# Blend_VCO.net
KiCad netlist of a schematic drawn in Altium Designer
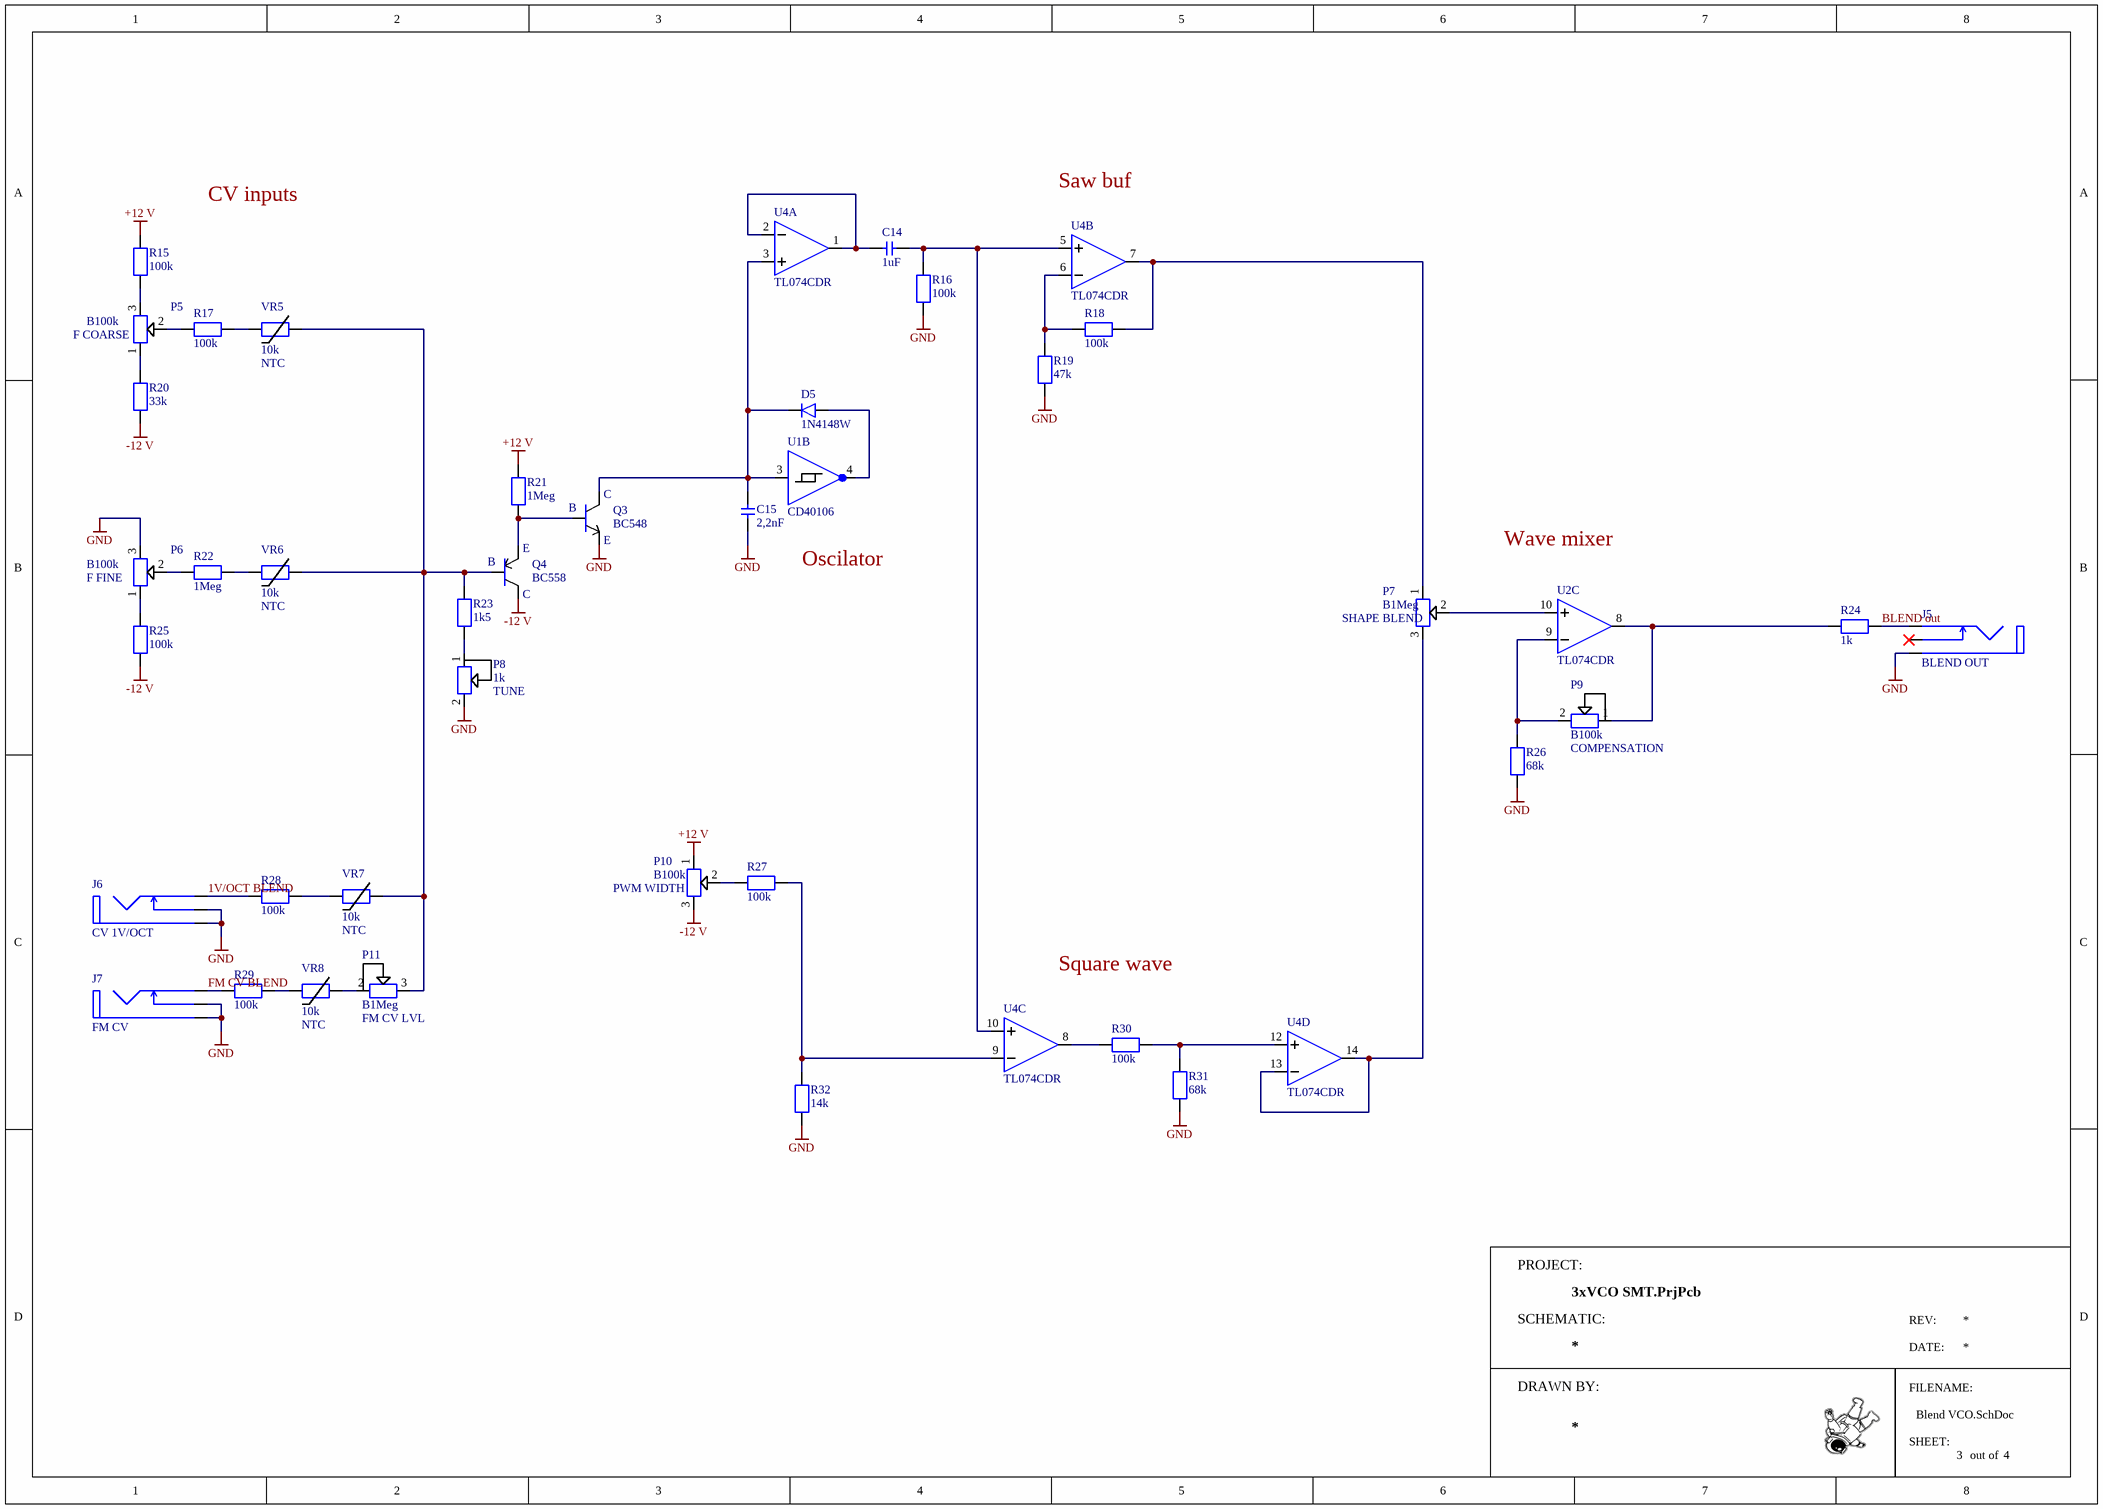
[diagram p0: Blend VCO.SchDoc]

(export (version "E")
  (design (tool "Eeschema 10.0.6"))
  (components
    (comp (ref "C14")
      (value "1uF")
      (footprint "Cap SMD 0805")
      (description "SMD Capacitor Non-Polarised 0805 Package")
      (fields (field (name "Comment") "CAP"))
      (libsource (lib "Generic components") (part "Capacitor SMD 0805"))
    )
    (comp (ref "C15")
      (value "2,2nF")
      (footprint "Cap SMD 0805")
      (description "SMD Capacitor Non-Polarised 0805 Package")
      (fields (field (name "Comment") "CAP"))
      (libsource (lib "Generic components") (part "Capacitor SMD 0805"))
    )
    (comp (ref "D5")
      (value "DIODE")
      (footprint "SOD-123")
      (description "Generic SMD Diode SOD123 Package")
      (fields (field (name "MODEL") "1N4148W"))
      (libsource (lib "Diodes") (part "Diode SMD SOD123"))
    )
    (comp (ref "J5")
      (value "JACK Mono")
      (footprint "PJ301M")
      (description "PJ301M Eurorack 3,5 mm Patch Socket PCB Mount")
      (fields (field (name "LABEL") "BLEND OUT"))
      (libsource (lib "Connectors") (part "PJ301M"))
    )
    (comp (ref "J6")
      (value "JACK Mono")
      (footprint "PJ301M")
      (description "PJ301M Eurorack 3,5 mm Patch Socket PCB Mount")
      (fields (field (name "LABEL") "CV 1V/OCT"))
      (libsource (lib "Connectors") (part "PJ301M"))
    )
    (comp (ref "J7")
      (value "JACK Mono")
      (footprint "PJ301M")
      (description "PJ301M Eurorack 3,5 mm Patch Socket PCB Mount")
      (fields (field (name "LABEL") "FM CV"))
      (libsource (lib "Connectors") (part "PJ301M"))
    )
    (comp (ref "P5")
      (value "B100k")
      (footprint "9 mm PCB Potentiometer")
      (description "PCB Mount 9mm Mono Potentiometer THT")
      (fields (field (name "PARAMETER") "F COARSE") (field (name "Comment") "Mono Pot"))
      (libsource (lib "Potentiometers") (part "Potentiometer 9 mm"))
    )
    (comp (ref "P6")
      (value "B100k")
      (footprint "9 mm PCB Potentiometer")
      (description "PCB Mount 9mm Mono Potentiometer THT")
      (fields (field (name "PARAMETER") "F FINE") (field (name "Comment") "Mono Pot"))
      (libsource (lib "Potentiometers") (part "Potentiometer 9 mm"))
    )
    (comp (ref "P7")
      (value "B1Meg")
      (footprint "9 mm PCB Potentiometer")
      (description "PCB Mount 9mm Mono Potentiometer THT")
      (fields (field (name "PARAMETER") "SHAPE BLEND") (field (name "Comment") "Mono Pot"))
      (libsource (lib "Potentiometers") (part "Potentiometer 9 mm"))
    )
    (comp (ref "P8")
      (value "1k")
      (footprint "Multiturn Potentiometer inline")
      (description "PCB Mount Multiturn Trimmer Potentiometer Top Adjustable as Variable Resistor Clockwise Increase")
      (fields (field (name "PARAMETER") "TUNE") (field (name "Comment") "VR"))
      (libsource (lib "Potentiometers") (part "VR A Multiturn THT"))
    )
    (comp (ref "P9")
      (value "B100k")
      (footprint "9 mm PCB Potentiometer")
      (description "PCB Mount 9mm Mono Potentiometer THT as Variable Resistor Clockwise Increase")
      (fields (field (name "PARAMETER") "COMPENSATION") (field (name "Comment") "VR"))
      (libsource (lib "Potentiometers") (part "VR A 9 mm"))
    )
    (comp (ref "P10")
      (value "B100k")
      (footprint "9 mm PCB Potentiometer")
      (description "PCB Mount 9mm Mono Potentiometer THT")
      (fields (field (name "PARAMETER") "PWM WIDTH") (field (name "Comment") "Mono Pot"))
      (libsource (lib "Potentiometers") (part "Potentiometer 9 mm"))
    )
    (comp (ref "P11")
      (value "B1Meg")
      (footprint "9 mm PCB Potentiometer")
      (description "PCB Mount 9mm Mono Potentiometer THT as Variable Resistor Clockwise Decrease")
      (fields (field (name "PARAMETER") "FM CV LVL") (field (name "Comment") "VR"))
      (libsource (lib "Potentiometers") (part "VR B 9 mm"))
    )
    (comp (ref "Q3")
      (value "BC548")
      (footprint "TO-92 wide")
      (description "BC548 NPN Transistor THT TO-92 Package")
      (libsource (lib "Transistors") (part "BC548"))
    )
    (comp (ref "Q4")
      (value "BC558")
      (footprint "TO-92 wide")
      (description "BC558 PNP Transistor THT TO-92 Package")
      (libsource (lib "Transistors") (part "BC558"))
    )
    (comp (ref "R15")
      (value "100k")
      (footprint "Resistor SMD 0805")
      (description "SMD Resistor 0805 package")
      (fields (field (name "Comment") "RES"))
      (libsource (lib "Generic components") (part "Resistor SMD 0805"))
    )
    (comp (ref "R16")
      (value "100k")
      (footprint "Resistor SMD 0805")
      (description "SMD Resistor 0805 package")
      (fields (field (name "Comment") "RES"))
      (libsource (lib "Generic components") (part "Resistor SMD 0805"))
    )
    (comp (ref "R17")
      (value "100k")
      (footprint "Resistor SMD 0805")
      (description "SMD Resistor 0805 package")
      (fields (field (name "Comment") "RES"))
      (libsource (lib "Generic components") (part "Resistor SMD 0805"))
    )
    (comp (ref "R18")
      (value "100k")
      (footprint "Resistor SMD 0805")
      (description "SMD Resistor 0805 package")
      (fields (field (name "Comment") "RES"))
      (libsource (lib "Generic components") (part "Resistor SMD 0805"))
    )
    (comp (ref "R19")
      (value "47k")
      (footprint "Resistor SMD 0805")
      (description "SMD Resistor 0805 package")
      (fields (field (name "Comment") "RES"))
      (libsource (lib "Generic components") (part "Resistor SMD 0805"))
    )
    (comp (ref "R20")
      (value "33k")
      (footprint "Resistor SMD 0805")
      (description "SMD Resistor 0805 package")
      (fields (field (name "Comment") "RES"))
      (libsource (lib "Generic components") (part "Resistor SMD 0805"))
    )
    (comp (ref "R21")
      (value "1Meg")
      (footprint "Resistor SMD 0805")
      (description "SMD Resistor 0805 package")
      (fields (field (name "Comment") "RES"))
      (libsource (lib "Generic components") (part "Resistor SMD 0805"))
    )
    (comp (ref "R22")
      (value "1Meg")
      (footprint "Resistor SMD 0805")
      (description "SMD Resistor 0805 package")
      (fields (field (name "Comment") "RES"))
      (libsource (lib "Generic components") (part "Resistor SMD 0805"))
    )
    (comp (ref "R23")
      (value "1k5")
      (footprint "Resistor SMD 0805")
      (description "SMD Resistor 0805 package")
      (fields (field (name "Comment") "RES"))
      (libsource (lib "Generic components") (part "Resistor SMD 0805"))
    )
    (comp (ref "R24")
      (value "1k")
      (footprint "Resistor SMD 0805")
      (description "SMD Resistor 0805 package")
      (fields (field (name "Comment") "RES"))
      (libsource (lib "Generic components") (part "Resistor SMD 0805"))
    )
    (comp (ref "R25")
      (value "100k")
      (footprint "Resistor SMD 0805")
      (description "SMD Resistor 0805 package")
      (fields (field (name "Comment") "RES"))
      (libsource (lib "Generic components") (part "Resistor SMD 0805"))
    )
    (comp (ref "R26")
      (value "68k")
      (footprint "Resistor SMD 0805")
      (description "SMD Resistor 0805 package")
      (fields (field (name "Comment") "RES"))
      (libsource (lib "Generic components") (part "Resistor SMD 0805"))
    )
    (comp (ref "R27")
      (value "100k")
      (footprint "Resistor SMD 0805")
      (description "SMD Resistor 0805 package")
      (fields (field (name "Comment") "RES"))
      (libsource (lib "Generic components") (part "Resistor SMD 0805"))
    )
    (comp (ref "R28")
      (value "100k")
      (footprint "Resistor SMD 0805")
      (description "SMD Resistor 0805 package")
      (fields (field (name "Comment") "RES"))
      (libsource (lib "Generic components") (part "Resistor SMD 0805"))
    )
    (comp (ref "R29")
      (value "100k")
      (footprint "Resistor SMD 0805")
      (description "SMD Resistor 0805 package")
      (fields (field (name "Comment") "RES"))
      (libsource (lib "Generic components") (part "Resistor SMD 0805"))
    )
    (comp (ref "R30")
      (value "100k")
      (footprint "Resistor SMD 0805")
      (description "SMD Resistor 0805 package")
      (fields (field (name "Comment") "RES"))
      (libsource (lib "Generic components") (part "Resistor SMD 0805"))
    )
    (comp (ref "R31")
      (value "68k")
      (footprint "Resistor SMD 0805")
      (description "SMD Resistor 0805 package")
      (fields (field (name "Comment") "RES"))
      (libsource (lib "Generic components") (part "Resistor SMD 0805"))
    )
    (comp (ref "R32")
      (value "14k")
      (footprint "Resistor SMD 0805")
      (description "SMD Resistor 0805 package")
      (fields (field (name "Comment") "RES"))
      (libsource (lib "Generic components") (part "Resistor SMD 0805"))
    )
    (comp (ref "U1")
      (value "CD40106")
      (footprint "DIP-14 socket")
      (description "CD40106 Hex Schmitt Trigger Inverter DIP-14 Package")
      (libsource (lib "ICs") (part "CD40106 DIP-14"))
    )
    (comp (ref "U2")
      (value "TL074CDR")
      (footprint "SOIC14")
      (description "TL074CDR Quad Op-Amp SOIC14 Package")
      (libsource (lib "") (part "TL074CDR SOIC14_1"))
    )
    (comp (ref "U4")
      (value "TL074CDR")
      (footprint "SOIC14")
      (description "TL074CDR Quad Op-Amp SOIC14 Package")
      (libsource (lib "") (part "TL074CDR SOIC14_1"))
    )
    (comp (ref "VR5")
      (value "NTC")
      (footprint "Thermistor SMD 0805")
      (description "SMD NTC Thermistor 0805 package")
      (fields (field (name "ALTIUM_VALUE") "10k"))
      (libsource (lib "Generic components") (part "Thermistor NTC SMD 0805"))
    )
    (comp (ref "VR6")
      (value "NTC")
      (footprint "Thermistor SMD 0805")
      (description "SMD NTC Thermistor 0805 package")
      (fields (field (name "ALTIUM_VALUE") "10k"))
      (libsource (lib "Generic components") (part "Thermistor NTC SMD 0805"))
    )
    (comp (ref "VR7")
      (value "NTC")
      (footprint "Thermistor SMD 0805")
      (description "SMD NTC Thermistor 0805 package")
      (fields (field (name "ALTIUM_VALUE") "10k"))
      (libsource (lib "Generic components") (part "Thermistor NTC SMD 0805"))
    )
    (comp (ref "VR8")
      (value "NTC")
      (footprint "Thermistor SMD 0805")
      (description "SMD NTC Thermistor 0805 package")
      (fields (field (name "ALTIUM_VALUE") "10k"))
      (libsource (lib "Generic components") (part "Thermistor NTC SMD 0805"))
    )
  )
  (nets
    (net (code "1") (name "+12 V") (class "Default")
      (node (ref "P10") (pin "1") (pintype "passive"))
      (node (ref "R15") (pin "2") (pintype "passive"))
      (node (ref "R21") (pin "1") (pintype "passive"))
    )
    (net (code "2") (name "-12 V") (class "Default")
      (node (ref "P10") (pin "3") (pintype "passive"))
      (node (ref "Q4") (pin "1") (pintype "passive"))
      (node (ref "R20") (pin "1") (pintype "passive"))
      (node (ref "R25") (pin "1") (pintype "passive"))
    )
    (net (code "3") (name "/1V{slash}OCT BLEND") (class "Default")
      (node (ref "J6") (pin "3") (pintype "passive"))
      (node (ref "R28") (pin "2") (pintype "passive"))
    )
    (net (code "4") (name "/BLEND out") (class "Default")
      (node (ref "J5") (pin "3") (pintype "passive"))
      (node (ref "R24") (pin "2") (pintype "passive"))
    )
    (net (code "5") (name "/FM CV BLEND") (class "Default")
      (node (ref "J7") (pin "3") (pintype "passive"))
      (node (ref "R29") (pin "2") (pintype "passive"))
    )
    (net (code "6") (name "GND") (class "Default")
      (node (ref "C15") (pin "1") (pintype "passive"))
      (node (ref "J5") (pin "1") (pintype "passive"))
      (node (ref "J6") (pin "1") (pintype "passive"))
      (node (ref "J6") (pin "2") (pintype "passive"))
      (node (ref "J7") (pin "1") (pintype "passive"))
      (node (ref "J7") (pin "2") (pintype "passive"))
      (node (ref "P6") (pin "3") (pintype "passive"))
      (node (ref "P8") (pin "2") (pintype "passive"))
      (node (ref "Q3") (pin "3") (pintype "passive"))
      (node (ref "R16") (pin "2") (pintype "passive"))
      (node (ref "R19") (pin "2") (pintype "passive"))
      (node (ref "R26") (pin "1") (pintype "passive"))
      (node (ref "R31") (pin "1") (pintype "passive"))
      (node (ref "R32") (pin "1") (pintype "passive"))
    )
    (net (code "7") (name "Net-(C14-Pad1)") (class "Default")
      (node (ref "C14") (pin "1") (pintype "passive"))
      (node (ref "R16") (pin "1") (pintype "passive"))
      (node (ref "U4") (pin "10") (pintype "passive"))
      (node (ref "U4") (pin "5") (pintype "passive"))
    )
    (net (code "8") (name "Net-(C14-Pad2)") (class "Default")
      (node (ref "C14") (pin "2") (pintype "passive"))
      (node (ref "U4") (pin "1") (pintype "passive"))
      (node (ref "U4") (pin "2") (pintype "passive"))
    )
    (net (code "9") (name "Net-(C15-Pad2)") (class "Default")
      (node (ref "C15") (pin "2") (pintype "passive"))
      (node (ref "D5") (pin "2") (pintype "passive"))
      (node (ref "Q3") (pin "1") (pintype "passive"))
      (node (ref "U1") (pin "3") (pintype "passive"))
      (node (ref "U4") (pin "3") (pintype "passive"))
    )
    (net (code "10") (name "Net-(D5-Pad1)") (class "Default")
      (node (ref "D5") (pin "1") (pintype "passive"))
      (node (ref "U1") (pin "4") (pintype "passive"))
    )
    (net (code "11") (name "Net-(P5-Pad1)") (class "Default")
      (node (ref "P5") (pin "1") (pintype "passive"))
      (node (ref "R20") (pin "2") (pintype "passive"))
    )
    (net (code "12") (name "Net-(P5-Pad2)") (class "Default")
      (node (ref "P5") (pin "2") (pintype "passive"))
      (node (ref "R17") (pin "2") (pintype "passive"))
    )
    (net (code "13") (name "Net-(P5-Pad3)") (class "Default")
      (node (ref "P5") (pin "3") (pintype "passive"))
      (node (ref "R15") (pin "1") (pintype "passive"))
    )
    (net (code "14") (name "Net-(P6-Pad1)") (class "Default")
      (node (ref "P6") (pin "1") (pintype "passive"))
      (node (ref "R25") (pin "2") (pintype "passive"))
    )
    (net (code "15") (name "Net-(P6-Pad2)") (class "Default")
      (node (ref "P6") (pin "2") (pintype "passive"))
      (node (ref "R22") (pin "2") (pintype "passive"))
    )
    (net (code "16") (name "Net-(P7-Pad1)") (class "Default")
      (node (ref "P7") (pin "1") (pintype "passive"))
      (node (ref "R18") (pin "2") (pintype "passive"))
      (node (ref "U4") (pin "7") (pintype "passive"))
    )
    (net (code "17") (name "Net-(P7-Pad2)") (class "Default")
      (node (ref "P7") (pin "2") (pintype "passive"))
      (node (ref "U2") (pin "10") (pintype "passive"))
    )
    (net (code "18") (name "Net-(P7-Pad3)") (class "Default")
      (node (ref "P7") (pin "3") (pintype "passive"))
      (node (ref "U4") (pin "13") (pintype "passive"))
      (node (ref "U4") (pin "14") (pintype "passive"))
    )
    (net (code "19") (name "Net-(P8-Pad1)") (class "Default")
      (node (ref "P8") (pin "1") (pintype "passive"))
      (node (ref "R23") (pin "2") (pintype "passive"))
    )
    (net (code "20") (name "Net-(P9-Pad1)") (class "Default")
      (node (ref "P9") (pin "1") (pintype "passive"))
      (node (ref "R24") (pin "1") (pintype "passive"))
      (node (ref "U2") (pin "8") (pintype "passive"))
    )
    (net (code "21") (name "Net-(P9-Pad2)") (class "Default")
      (node (ref "P9") (pin "2") (pintype "passive"))
      (node (ref "R26") (pin "2") (pintype "passive"))
      (node (ref "U2") (pin "9") (pintype "passive"))
    )
    (net (code "22") (name "Net-(P10-Pad2)") (class "Default")
      (node (ref "P10") (pin "2") (pintype "passive"))
      (node (ref "R27") (pin "1") (pintype "passive"))
    )
    (net (code "23") (name "Net-(P11-Pad2)") (class "Default")
      (node (ref "P11") (pin "2") (pintype "passive"))
      (node (ref "VR8") (pin "2") (pintype "passive"))
    )
    (net (code "24") (name "Net-(P11-Pad3)") (class "Default")
      (node (ref "P11") (pin "3") (pintype "passive"))
      (node (ref "Q4") (pin "2") (pintype "passive"))
      (node (ref "R23") (pin "1") (pintype "passive"))
      (node (ref "VR5") (pin "2") (pintype "passive"))
      (node (ref "VR6") (pin "2") (pintype "passive"))
      (node (ref "VR7") (pin "2") (pintype "passive"))
    )
    (net (code "25") (name "Net-(Q3-Pad2)") (class "Default")
      (node (ref "Q3") (pin "2") (pintype "passive"))
      (node (ref "Q4") (pin "3") (pintype "passive"))
      (node (ref "R21") (pin "2") (pintype "passive"))
    )
    (net (code "26") (name "Net-(R17-Pad1)") (class "Default")
      (node (ref "R17") (pin "1") (pintype "passive"))
      (node (ref "VR5") (pin "1") (pintype "passive"))
    )
    (net (code "27") (name "Net-(R18-Pad1)") (class "Default")
      (node (ref "R18") (pin "1") (pintype "passive"))
      (node (ref "R19") (pin "1") (pintype "passive"))
      (node (ref "U4") (pin "6") (pintype "passive"))
    )
    (net (code "28") (name "Net-(R22-Pad1)") (class "Default")
      (node (ref "R22") (pin "1") (pintype "passive"))
      (node (ref "VR6") (pin "1") (pintype "passive"))
    )
    (net (code "29") (name "Net-(R27-Pad2)") (class "Default")
      (node (ref "R27") (pin "2") (pintype "passive"))
      (node (ref "R32") (pin "2") (pintype "passive"))
      (node (ref "U4") (pin "9") (pintype "passive"))
    )
    (net (code "30") (name "Net-(R28-Pad1)") (class "Default")
      (node (ref "R28") (pin "1") (pintype "passive"))
      (node (ref "VR7") (pin "1") (pintype "passive"))
    )
    (net (code "31") (name "Net-(R29-Pad1)") (class "Default")
      (node (ref "R29") (pin "1") (pintype "passive"))
      (node (ref "VR8") (pin "1") (pintype "passive"))
    )
    (net (code "32") (name "Net-(R30-Pad1)") (class "Default")
      (node (ref "R30") (pin "1") (pintype "passive"))
      (node (ref "U4") (pin "8") (pintype "passive"))
    )
    (net (code "33") (name "Net-(R30-Pad2)") (class "Default")
      (node (ref "R30") (pin "2") (pintype "passive"))
      (node (ref "R31") (pin "2") (pintype "passive"))
      (node (ref "U4") (pin "12") (pintype "passive"))
    )
    (net (code "34") (name "unconnected-(J5-Pad2)") (class "Default")
      (node (ref "J5") (pin "2") (pintype "passive+no_connect"))
    )
  )
)
